# multiline_shield.net
KiCad netlist of a schematic drawn in EAGLE
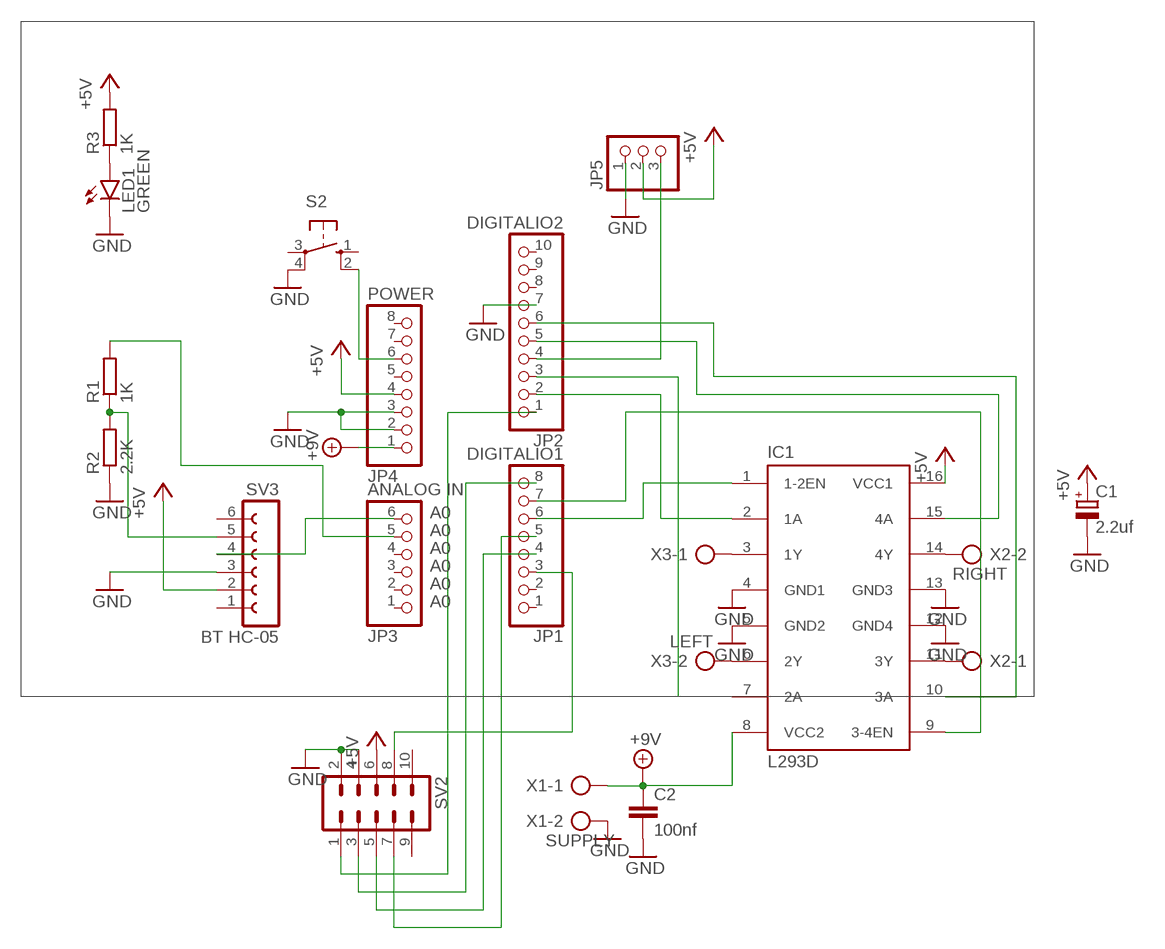
[diagram p0: schematic, sheet 1]

(export (version "E")
  (design (tool "Eeschema 10.0.6"))
  (components
    (comp (ref "C1")
      (value "2.2uf")
      (footprint "eagle-import:E2,5-6")
      (libsource (lib "eagle-import") (part "CPOL-EUE2.5-6"))
    )
    (comp (ref "C2")
      (value "100nf")
      (footprint "eagle-import:C025-025X050")
      (libsource (lib "eagle-import") (part "C-EU025-025X050"))
    )
    (comp (ref "IC1")
      (value "L293D")
      (footprint "eagle-import:DIL16")
      (libsource (lib "eagle-import") (part "L293D"))
    )
    (comp (ref "JP1")
      (value "DIGITALIO1")
      (footprint "eagle-import:1X08")
      (libsource (lib "eagle-import") (part "PINHD-1X8"))
    )
    (comp (ref "JP2")
      (value "DIGITALIO2")
      (footprint "eagle-import:1X10")
      (libsource (lib "eagle-import") (part "PINHD-1X10"))
    )
    (comp (ref "JP3")
      (value "ANALOG IN")
      (footprint "eagle-import:1X06")
      (libsource (lib "eagle-import") (part "PINHD-1X6"))
    )
    (comp (ref "JP4")
      (value "POWER")
      (footprint "eagle-import:1X08")
      (libsource (lib "eagle-import") (part "PINHD-1X8"))
    )
    (comp (ref "JP5")
      (value "PINHD-1X3")
      (footprint "eagle-import:1X03")
      (libsource (lib "eagle-import") (part "PINHD-1X3"))
    )
    (comp (ref "LED1")
      (value "GREEN")
      (footprint "eagle-import:LED3MM")
      (libsource (lib "eagle-import") (part "LED3MM"))
    )
    (comp (ref "R1")
      (value "1K")
      (footprint "eagle-import:0207_10")
      (libsource (lib "eagle-import") (part "R-EU_0207/10"))
    )
    (comp (ref "R2")
      (value "2.2K")
      (footprint "eagle-import:0207_10")
      (libsource (lib "eagle-import") (part "R-EU_0207/10"))
    )
    (comp (ref "R3")
      (value "1K")
      (footprint "eagle-import:0207_10")
      (libsource (lib "eagle-import") (part "R-EU_0207/10"))
    )
    (comp (ref "S2")
      (value "10-XX")
      (footprint "eagle-import:B3F-10XX")
      (fields (field (name "MPN") "B3F-1000"))
      (libsource (lib "eagle-import") (part "10-XX"))
    )
    (comp (ref "SV2")
      (value "ML10")
      (footprint "eagle-import:ML10")
      (libsource (lib "eagle-import") (part "ML10"))
    )
    (comp (ref "SV3")
      (value "BT HC-05")
      (footprint "eagle-import:FE06")
      (libsource (lib "eagle-import") (part "FE06-1"))
    )
    (comp (ref "X1")
      (value "SUPPLY")
      (footprint "eagle-import:AK300_2")
      (libsource (lib "eagle-import") (part "AK300/2"))
    )
    (comp (ref "X2")
      (value "RIGHT")
      (footprint "eagle-import:AK300_2")
      (libsource (lib "eagle-import") (part "AK300/2"))
    )
    (comp (ref "X3")
      (value "LEFT")
      (footprint "eagle-import:AK300_2")
      (libsource (lib "eagle-import") (part "AK300/2"))
    )
  )
  (nets
    (net (code "1") (name "+5V") (class "Default")
      (node (ref "C1") (pin "+") (pinfunction "+_+") (pintype "passive"))
      (node (ref "IC1") (pin "16") (pinfunction "VCC1_16") (pintype "power_in"))
      (node (ref "JP4") (pin "4") (pinfunction "4_4") (pintype "passive"))
      (node (ref "JP5") (pin "2") (pinfunction "2_2") (pintype "passive"))
      (node (ref "R3") (pin "2") (pinfunction "2_2") (pintype "passive"))
      (node (ref "SV2") (pin "6") (pinfunction "6_6") (pintype "passive"))
      (node (ref "SV3") (pin "2") (pinfunction "2_2") (pintype "passive"))
    )
    (net (code "2") (name "+9V") (class "Default")
      (node (ref "C2") (pin "1") (pinfunction "1_1") (pintype "passive"))
      (node (ref "IC1") (pin "8") (pinfunction "VCC2_8") (pintype "power_in"))
      (node (ref "JP4") (pin "1") (pinfunction "1_1") (pintype "passive"))
      (node (ref "X1") (pin "1") (pinfunction "KL_1") (pintype "passive"))
    )
    (net (code "3") (name "GND") (class "Default")
      (node (ref "C1") (pin "-") (pinfunction "-_-") (pintype "passive"))
      (node (ref "C2") (pin "2") (pinfunction "2_2") (pintype "passive"))
      (node (ref "IC1") (pin "12") (pinfunction "GND4_12") (pintype "power_in"))
      (node (ref "IC1") (pin "13") (pinfunction "GND3_13") (pintype "power_in"))
      (node (ref "IC1") (pin "4") (pinfunction "GND1_4") (pintype "power_in"))
      (node (ref "IC1") (pin "5") (pinfunction "GND2_5") (pintype "power_in"))
      (node (ref "JP2") (pin "7") (pinfunction "7_7") (pintype "passive"))
      (node (ref "JP4") (pin "2") (pinfunction "2_2") (pintype "passive"))
      (node (ref "JP4") (pin "3") (pinfunction "3_3") (pintype "passive"))
      (node (ref "JP5") (pin "1") (pinfunction "1_1") (pintype "passive"))
      (node (ref "LED1") (pin "K") (pinfunction "C_K") (pintype "passive"))
      (node (ref "R2") (pin "1") (pinfunction "1_1") (pintype "passive"))
      (node (ref "S2") (pin "4") (pinfunction "P1_4") (pintype "passive"))
      (node (ref "SV2") (pin "2") (pinfunction "2_2") (pintype "passive"))
      (node (ref "SV2") (pin "4") (pinfunction "4_4") (pintype "passive"))
      (node (ref "SV3") (pin "3") (pinfunction "3_3") (pintype "passive"))
      (node (ref "X1") (pin "2") (pinfunction "KL_2") (pintype "passive"))
    )
    (net (code "4") (name "Net-(IC1-1-2EN)") (class "Default")
      (node (ref "IC1") (pin "1") (pinfunction "1-2EN_1") (pintype "input"))
      (node (ref "JP1") (pin "6") (pinfunction "6_6") (pintype "passive"))
    )
    (net (code "5") (name "Net-(IC1-1A)") (class "Default")
      (node (ref "IC1") (pin "2") (pinfunction "1A_2") (pintype "input"))
      (node (ref "JP2") (pin "2") (pinfunction "2_2") (pintype "passive"))
    )
    (net (code "6") (name "Net-(IC1-1Y)") (class "Default")
      (node (ref "IC1") (pin "3") (pinfunction "1Y_3") (pintype "output"))
      (node (ref "X3") (pin "1") (pinfunction "KL_1") (pintype "passive"))
    )
    (net (code "7") (name "Net-(IC1-2A)") (class "Default")
      (node (ref "IC1") (pin "7") (pinfunction "2A_7") (pintype "input"))
      (node (ref "JP2") (pin "3") (pinfunction "3_3") (pintype "passive"))
    )
    (net (code "8") (name "Net-(IC1-2Y)") (class "Default")
      (node (ref "IC1") (pin "6") (pinfunction "2Y_6") (pintype "output"))
      (node (ref "X3") (pin "2") (pinfunction "KL_2") (pintype "passive"))
    )
    (net (code "9") (name "Net-(IC1-3-4EN)") (class "Default")
      (node (ref "IC1") (pin "9") (pinfunction "3-4EN_9") (pintype "input"))
      (node (ref "JP1") (pin "7") (pinfunction "7_7") (pintype "passive"))
    )
    (net (code "10") (name "Net-(IC1-3A)") (class "Default")
      (node (ref "IC1") (pin "10") (pinfunction "3A_10") (pintype "input"))
      (node (ref "JP2") (pin "6") (pinfunction "6_6") (pintype "passive"))
    )
    (net (code "11") (name "Net-(IC1-3Y)") (class "Default")
      (node (ref "IC1") (pin "11") (pinfunction "3Y_11") (pintype "output"))
      (node (ref "X2") (pin "1") (pinfunction "KL_1") (pintype "passive"))
    )
    (net (code "12") (name "Net-(IC1-4A)") (class "Default")
      (node (ref "IC1") (pin "15") (pinfunction "4A_15") (pintype "input"))
      (node (ref "JP2") (pin "5") (pinfunction "5_5") (pintype "passive"))
    )
    (net (code "13") (name "Net-(IC1-4Y)") (class "Default")
      (node (ref "IC1") (pin "14") (pinfunction "4Y_14") (pintype "output"))
      (node (ref "X2") (pin "2") (pinfunction "KL_2") (pintype "passive"))
    )
    (net (code "14") (name "Net-(JP1-Pad3)") (class "Default")
      (node (ref "JP1") (pin "3") (pinfunction "3_3") (pintype "passive"))
      (node (ref "SV2") (pin "8") (pinfunction "8_8") (pintype "passive"))
    )
    (net (code "15") (name "Net-(JP1-Pad4)") (class "Default")
      (node (ref "JP1") (pin "4") (pinfunction "4_4") (pintype "passive"))
      (node (ref "SV2") (pin "5") (pinfunction "5_5") (pintype "passive"))
    )
    (net (code "16") (name "Net-(JP1-Pad5)") (class "Default")
      (node (ref "JP1") (pin "5") (pinfunction "5_5") (pintype "passive"))
      (node (ref "SV2") (pin "7") (pinfunction "7_7") (pintype "passive"))
    )
    (net (code "17") (name "Net-(JP1-Pad8)") (class "Default")
      (node (ref "JP1") (pin "8") (pinfunction "8_8") (pintype "passive"))
      (node (ref "SV2") (pin "3") (pinfunction "3_3") (pintype "passive"))
    )
    (net (code "18") (name "Net-(JP2-Pad1)") (class "Default")
      (node (ref "JP2") (pin "1") (pinfunction "1_1") (pintype "passive"))
      (node (ref "SV2") (pin "1") (pinfunction "1_1") (pintype "passive"))
    )
    (net (code "19") (name "Net-(JP2-Pad4)") (class "Default")
      (node (ref "JP2") (pin "4") (pinfunction "4_4") (pintype "passive"))
      (node (ref "JP5") (pin "3") (pinfunction "3_3") (pintype "passive"))
    )
    (net (code "20") (name "Net-(JP3-Pad5)") (class "Default")
      (node (ref "JP3") (pin "5") (pinfunction "5_5") (pintype "passive"))
      (node (ref "R1") (pin "2") (pinfunction "2_2") (pintype "passive"))
    )
    (net (code "21") (name "Net-(JP3-Pad6)") (class "Default")
      (node (ref "JP3") (pin "6") (pinfunction "6_6") (pintype "passive"))
      (node (ref "SV3") (pin "4") (pinfunction "4_4") (pintype "passive"))
    )
    (net (code "22") (name "Net-(LED1-PadA)") (class "Default")
      (node (ref "LED1") (pin "A") (pinfunction "A_A") (pintype "passive"))
      (node (ref "R3") (pin "1") (pinfunction "1_1") (pintype "passive"))
    )
    (net (code "23") (name "Net-(R1-Pad1)") (class "Default")
      (node (ref "R1") (pin "1") (pinfunction "1_1") (pintype "passive"))
      (node (ref "R2") (pin "2") (pinfunction "2_2") (pintype "passive"))
      (node (ref "SV3") (pin "5") (pinfunction "5_5") (pintype "passive"))
    )
    (net (code "24") (name "Net-(S2-S1)") (class "Default")
      (node (ref "JP4") (pin "6") (pinfunction "6_6") (pintype "passive"))
      (node (ref "S2") (pin "2") (pinfunction "S1_2") (pintype "passive"))
    )
    (net (code "25") (name "unconnected-(JP1-Pad1)") (class "Default")
      (node (ref "JP1") (pin "1") (pinfunction "1_1") (pintype "passive"))
    )
    (net (code "26") (name "unconnected-(JP1-Pad2)") (class "Default")
      (node (ref "JP1") (pin "2") (pinfunction "2_2") (pintype "passive"))
    )
    (net (code "27") (name "unconnected-(JP2-Pad8)") (class "Default")
      (node (ref "JP2") (pin "8") (pinfunction "8_8") (pintype "passive"))
    )
    (net (code "28") (name "unconnected-(JP2-Pad9)") (class "Default")
      (node (ref "JP2") (pin "9") (pinfunction "9_9") (pintype "passive"))
    )
    (net (code "29") (name "unconnected-(JP2-Pad10)") (class "Default")
      (node (ref "JP2") (pin "10") (pinfunction "10_10") (pintype "passive"))
    )
    (net (code "30") (name "unconnected-(JP3-Pad1)") (class "Default")
      (node (ref "JP3") (pin "1") (pinfunction "1_1") (pintype "passive"))
    )
    (net (code "31") (name "unconnected-(JP3-Pad2)") (class "Default")
      (node (ref "JP3") (pin "2") (pinfunction "2_2") (pintype "passive"))
    )
    (net (code "32") (name "unconnected-(JP3-Pad3)") (class "Default")
      (node (ref "JP3") (pin "3") (pinfunction "3_3") (pintype "passive"))
    )
    (net (code "33") (name "unconnected-(JP3-Pad4)") (class "Default")
      (node (ref "JP3") (pin "4") (pinfunction "4_4") (pintype "passive"))
    )
    (net (code "34") (name "unconnected-(JP4-Pad5)") (class "Default")
      (node (ref "JP4") (pin "5") (pinfunction "5_5") (pintype "passive"))
    )
    (net (code "35") (name "unconnected-(JP4-Pad7)") (class "Default")
      (node (ref "JP4") (pin "7") (pinfunction "7_7") (pintype "passive"))
    )
    (net (code "36") (name "unconnected-(JP4-Pad8)") (class "Default")
      (node (ref "JP4") (pin "8") (pinfunction "8_8") (pintype "passive"))
    )
    (net (code "37") (name "unconnected-(S2-P-Pad3)") (class "Default")
      (node (ref "S2") (pin "3") (pinfunction "P_3") (pintype "passive"))
    )
    (net (code "38") (name "unconnected-(S2-S-Pad1)") (class "Default")
      (node (ref "S2") (pin "1") (pinfunction "S_1") (pintype "passive"))
    )
    (net (code "39") (name "unconnected-(SV2-Pad9)") (class "Default")
      (node (ref "SV2") (pin "9") (pinfunction "9_9") (pintype "passive"))
    )
    (net (code "40") (name "unconnected-(SV2-Pad10)") (class "Default")
      (node (ref "SV2") (pin "10") (pinfunction "10_10") (pintype "passive"))
    )
    (net (code "41") (name "unconnected-(SV3-Pad1)") (class "Default")
      (node (ref "SV3") (pin "1") (pinfunction "1_1") (pintype "passive"))
    )
    (net (code "42") (name "unconnected-(SV3-Pad6)") (class "Default")
      (node (ref "SV3") (pin "6") (pinfunction "6_6") (pintype "passive"))
    )
  )
)
